# MagicWandFinal.net
KiCad netlist of a schematic drawn in Altium Designer
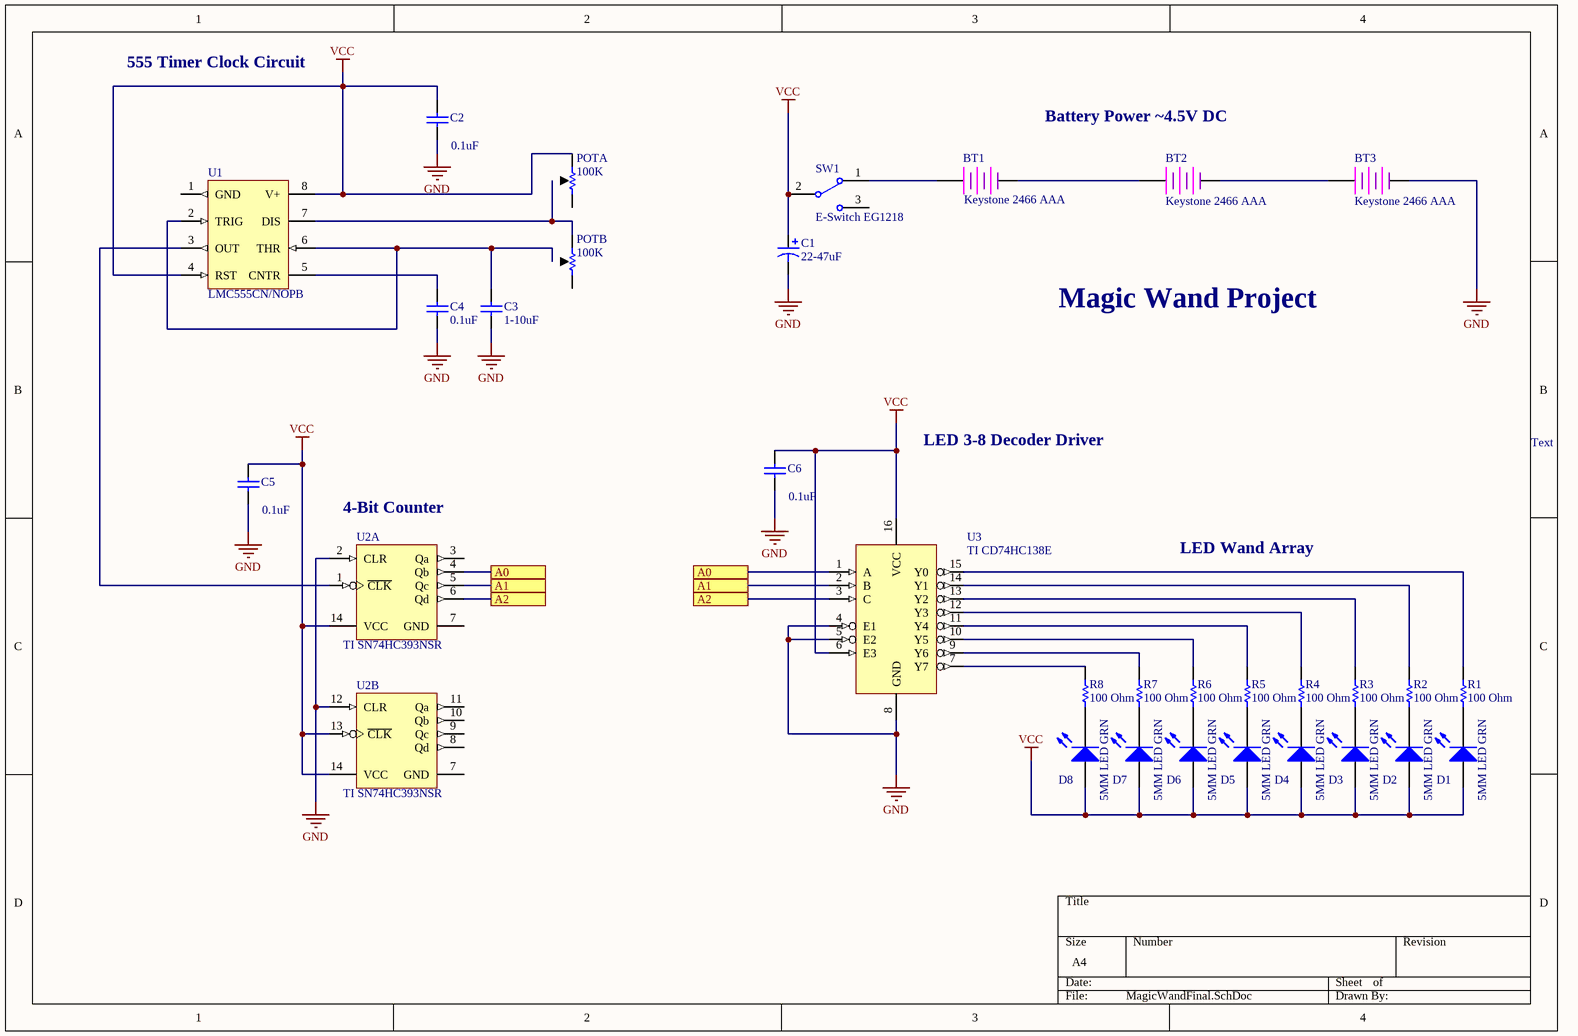
[diagram p0: MagicWandFinal.SchDoc]

(export (version "E")
  (design (tool "Eeschema 10.0.6"))
  (components
    (comp (ref "BT1")
      (value "Keystone 2466 AAA")
      (footprint "PCB-2466")
      (description "Battery holder, AAA, 1 cell, PC mount")
      (libsource (lib "My Personal Space") (part "SYM-2466"))
    )
    (comp (ref "BT2")
      (value "Keystone 2466 AAA")
      (footprint "PCB-2466")
      (description "Battery holder, AAA, 1 cell, PC mount")
      (libsource (lib "My Personal Space") (part "SYM-2466"))
    )
    (comp (ref "BT3")
      (value "Keystone 2466 AAA")
      (footprint "PCB-2466")
      (description "Battery holder, AAA, 1 cell, PC mount")
      (libsource (lib "My Personal Space") (part "SYM-2466"))
    )
    (comp (ref "C1")
      (value "22-47uF")
      (footprint "PCB-nq6yd78wv7rl8ojp8omb-1")
      (description "Cap Aluminum 10uF 16V 20% (4 X 7mm) Cylindrical 18mA 7000 hr 105°C T/R")
      (fields (field (name "MANUFACTURER PART NUMBER") "UCB1C100MCL1GS"))
      (libsource (lib "My Personal Space") (part "SYM-119dd9bbe86bce5a-1"))
    )
    (comp (ref "C2")
      (value "0.1uF")
      (footprint "PCB-ql28fbuo3tond8refhb5-1")
      (description "K 100nF Ceramic Multilayer Capacitor, 50 V dc, +125degC, X7R Dielectric, +/-10%")
      (libsource (lib "My Personal Space") (part "SYM-1272d9258f2acdb5-2"))
    )
    (comp (ref "C3")
      (value "1-10uF")
      (footprint "PCB-ql28fbuo3tond8refhb5-1")
      (description "K 100nF Ceramic Multilayer Capacitor, 50 V dc, +125degC, X7R Dielectric, +/-10%")
      (libsource (lib "My Personal Space") (part "SYM-1272d9258f2acdb5-2"))
    )
    (comp (ref "C4")
      (value "0.1uF")
      (footprint "PCB-ql28fbuo3tond8refhb5-1")
      (description "K 100nF Ceramic Multilayer Capacitor, 50 V dc, +125degC, X7R Dielectric, +/-10%")
      (libsource (lib "My Personal Space") (part "SYM-1272d9258f2acdb5-2"))
    )
    (comp (ref "C5")
      (value "0.1uF")
      (footprint "PCB-ql28fbuo3tond8refhb5-1")
      (description "K 100nF Ceramic Multilayer Capacitor, 50 V dc, +125degC, X7R Dielectric, +/-10%")
      (libsource (lib "My Personal Space") (part "SYM-1272d9258f2acdb5-2"))
    )
    (comp (ref "C6")
      (value "0.1uF")
      (footprint "PCB-ql28fbuo3tond8refhb5-1")
      (description "K 100nF Ceramic Multilayer Capacitor, 50 V dc, +125degC, X7R Dielectric, +/-10%")
      (libsource (lib "My Personal Space") (part "SYM-1272d9258f2acdb5-2"))
    )
    (comp (ref "D1")
      (value "5MM LED GRN")
      (footprint "PCB-b5vk7vz0xhkw7l0fnova-1")
      (description "LED Uni-Color Green 2-Pin T-1 3/4 Bulk")
      (fields
        (field (name "MANUFACTURER PART NUMBER") "C503B-GCN-CY0C0791")
        (field (name "MANUFACTURER") "Cree")
      )
      (libsource (lib "My Personal Space") (part "SYM-92bb5b2eff764d7c-1"))
    )
    (comp (ref "D2")
      (value "5MM LED GRN")
      (footprint "PCB-b5vk7vz0xhkw7l0fnova-1")
      (description "LED Uni-Color Green 2-Pin T-1 3/4 Bulk")
      (fields
        (field (name "MANUFACTURER PART NUMBER") "C503B-GCN-CY0C0791")
        (field (name "MANUFACTURER") "Cree")
      )
      (libsource (lib "My Personal Space") (part "SYM-92bb5b2eff764d7c-1"))
    )
    (comp (ref "D3")
      (value "5MM LED GRN")
      (footprint "PCB-b5vk7vz0xhkw7l0fnova-1")
      (description "LED Uni-Color Green 2-Pin T-1 3/4 Bulk")
      (fields
        (field (name "MANUFACTURER PART NUMBER") "C503B-GCN-CY0C0791")
        (field (name "MANUFACTURER") "Cree")
      )
      (libsource (lib "My Personal Space") (part "SYM-92bb5b2eff764d7c-1"))
    )
    (comp (ref "D4")
      (value "5MM LED GRN")
      (footprint "PCB-b5vk7vz0xhkw7l0fnova-1")
      (description "LED Uni-Color Green 2-Pin T-1 3/4 Bulk")
      (fields
        (field (name "MANUFACTURER PART NUMBER") "C503B-GCN-CY0C0791")
        (field (name "MANUFACTURER") "Cree")
      )
      (libsource (lib "My Personal Space") (part "SYM-92bb5b2eff764d7c-1"))
    )
    (comp (ref "D5")
      (value "5MM LED GRN")
      (footprint "PCB-b5vk7vz0xhkw7l0fnova-1")
      (description "LED Uni-Color Green 2-Pin T-1 3/4 Bulk")
      (fields
        (field (name "MANUFACTURER PART NUMBER") "C503B-GCN-CY0C0791")
        (field (name "MANUFACTURER") "Cree")
      )
      (libsource (lib "My Personal Space") (part "SYM-92bb5b2eff764d7c-1"))
    )
    (comp (ref "D6")
      (value "5MM LED GRN")
      (footprint "PCB-b5vk7vz0xhkw7l0fnova-1")
      (description "LED Uni-Color Green 2-Pin T-1 3/4 Bulk")
      (fields
        (field (name "MANUFACTURER PART NUMBER") "C503B-GCN-CY0C0791")
        (field (name "MANUFACTURER") "Cree")
      )
      (libsource (lib "My Personal Space") (part "SYM-92bb5b2eff764d7c-1"))
    )
    (comp (ref "D7")
      (value "5MM LED GRN")
      (footprint "PCB-b5vk7vz0xhkw7l0fnova-1")
      (description "LED Uni-Color Green 2-Pin T-1 3/4 Bulk")
      (fields
        (field (name "MANUFACTURER PART NUMBER") "C503B-GCN-CY0C0791")
        (field (name "MANUFACTURER") "Cree")
      )
      (libsource (lib "My Personal Space") (part "SYM-92bb5b2eff764d7c-1"))
    )
    (comp (ref "D8")
      (value "5MM LED GRN")
      (footprint "PCB-b5vk7vz0xhkw7l0fnova-1")
      (description "LED Uni-Color Green 2-Pin T-1 3/4 Bulk")
      (fields
        (field (name "MANUFACTURER PART NUMBER") "C503B-GCN-CY0C0791")
        (field (name "MANUFACTURER") "Cree")
      )
      (libsource (lib "My Personal Space") (part "SYM-92bb5b2eff764d7c-1"))
    )
    (comp (ref "POTA")
      (value "100K")
      (footprint "PCB-yu8b13vw5bhotm5v9joo-1")
      (description "Res Cermet Trimmer 200K Ohm 10% 1/2W 1(Elec)/1(Mech)Turn 2.6mm (7 X 7 X 5.8mm) Pin Thru-Hole Bulk")
      (fields (field (name "MANUFACTURER PART NUMBER") "CT-6EP204"))
      (libsource (lib "My Personal Space") (part "SYM-1c6ed013efbec3a9-1"))
    )
    (comp (ref "POTB")
      (value "100K")
      (footprint "PCB-yu8b13vw5bhotm5v9joo-1")
      (description "Res Cermet Trimmer 200K Ohm 10% 1/2W 1(Elec)/1(Mech)Turn 2.6mm (7 X 7 X 5.8mm) Pin Thru-Hole Bulk")
      (fields (field (name "MANUFACTURER PART NUMBER") "CT-6EP204"))
      (libsource (lib "My Personal Space") (part "SYM-1c6ed013efbec3a9-1"))
    )
    (comp (ref "R1")
      (value "100 Ohm")
      (footprint "PCB-0jk5y5qyb1smy9vf6b7t-1")
      (description "Res, 1K, 250mW, 5%, Axial")
      (libsource (lib "My Personal Space") (part "SYM-db3e1311f37e04f9-4"))
    )
    (comp (ref "R2")
      (value "100 Ohm")
      (footprint "PCB-0jk5y5qyb1smy9vf6b7t-1")
      (description "Res, 1K, 250mW, 5%, Axial")
      (libsource (lib "My Personal Space") (part "SYM-db3e1311f37e04f9-4"))
    )
    (comp (ref "R3")
      (value "100 Ohm")
      (footprint "PCB-0jk5y5qyb1smy9vf6b7t-1")
      (description "Res, 1K, 250mW, 5%, Axial")
      (libsource (lib "My Personal Space") (part "SYM-db3e1311f37e04f9-4"))
    )
    (comp (ref "R4")
      (value "100 Ohm")
      (footprint "PCB-0jk5y5qyb1smy9vf6b7t-1")
      (description "Res, 1K, 250mW, 5%, Axial")
      (libsource (lib "My Personal Space") (part "SYM-db3e1311f37e04f9-4"))
    )
    (comp (ref "R5")
      (value "100 Ohm")
      (footprint "PCB-0jk5y5qyb1smy9vf6b7t-1")
      (description "Res, 1K, 250mW, 5%, Axial")
      (libsource (lib "My Personal Space") (part "SYM-db3e1311f37e04f9-4"))
    )
    (comp (ref "R6")
      (value "100 Ohm")
      (footprint "PCB-0jk5y5qyb1smy9vf6b7t-1")
      (description "Res, 1K, 250mW, 5%, Axial")
      (libsource (lib "My Personal Space") (part "SYM-db3e1311f37e04f9-4"))
    )
    (comp (ref "R7")
      (value "100 Ohm")
      (footprint "PCB-0jk5y5qyb1smy9vf6b7t-1")
      (description "Res, 1K, 250mW, 5%, Axial")
      (libsource (lib "My Personal Space") (part "SYM-db3e1311f37e04f9-4"))
    )
    (comp (ref "R8")
      (value "100 Ohm")
      (footprint "PCB-0jk5y5qyb1smy9vf6b7t-1")
      (description "Res, 1K, 250mW, 5%, Axial")
      (libsource (lib "My Personal Space") (part "SYM-db3e1311f37e04f9-4"))
    )
    (comp (ref "SW1")
      (value "E-Switch EG1218")
      (footprint "ESWI-EG1218_V")
      (description "Slide Switch, 500 V, -20 to 70 degC, 3-Pin THD, RoHS")
      (fields (field (name "MANUFACTURER PART NUMBER") "EG1218"))
      (libsource (lib "My Personal Space") (part "SW-SPDT-3_B"))
    )
    (comp (ref "U1")
      (value "LMC555CN/NOPB")
      (footprint "TI-D8_L")
      (description "World’s smallest 555 timer with low power, high accuracy and a Fmax of 3MHz 8-SOIC -40 to 85")
      (fields (field (name "MANUFACTURER PART NUMBER") "LMC555CMX/NOPB"))
      (libsource (lib "My Personal Space") (part "INF-TLE5012BE5000-PG-DSO-8-16-8"))
    )
    (comp (ref "U2")
      (value "TI SN74HC393NSR")
      (footprint "SOIC-SL14_N")
      (description "Counter/Divider Dual 4-Bit Binary UP 14-Pin SOP T/R   SMD")
      (fields (field (name "MANUFACTURER PART NUMBER") "SN74HC393NSR"))
      (libsource (lib "My Personal Space") (part "SYM-3c53f5596157e394-1"))
    )
    (comp (ref "U3")
      (value "TI CD74HC138E")
      (footprint "PCB-iqyivjlmuk83cucpld0n-1")
      (description "TEXAS INSTRUMENTS   CD74HC138E   Logic Type:Decoder / Demultiplexer")
      (fields
        (field (name "MANUFACTURER") "Texas Instruments")
        (field (name "MANUFACTURER PART NUMBER") "CD74HC138E")
      )
      (libsource (lib "My Personal Space") (part "SYM-1166716-1"))
    )
  )
  (nets
    (net (code "1") (name "/A0") (class "Default")
      (node (ref "U2") (pin "4") (pinfunction "Qb_4") (pintype "output"))
      (node (ref "U3") (pin "1") (pinfunction "A_1") (pintype "input"))
    )
    (net (code "2") (name "/A1") (class "Default")
      (node (ref "U2") (pin "5") (pinfunction "Qc_5") (pintype "output"))
      (node (ref "U3") (pin "2") (pinfunction "B_2") (pintype "input"))
    )
    (net (code "3") (name "/A2") (class "Default")
      (node (ref "U2") (pin "6") (pinfunction "Qd_6") (pintype "output"))
      (node (ref "U3") (pin "3") (pinfunction "C_3") (pintype "input"))
    )
    (net (code "4") (name "GND") (class "Default")
      (node (ref "BT3") (pin "2") (pinfunction "-_2") (pintype "passive"))
      (node (ref "C1") (pin "2") (pinfunction "2_2") (pintype "passive"))
      (node (ref "C2") (pin "1") (pinfunction "1_1") (pintype "passive"))
      (node (ref "C3") (pin "1") (pinfunction "1_1") (pintype "passive"))
      (node (ref "C4") (pin "1") (pinfunction "1_1") (pintype "passive"))
      (node (ref "C5") (pin "1") (pinfunction "1_1") (pintype "passive"))
      (node (ref "C6") (pin "1") (pinfunction "1_1") (pintype "passive"))
      (node (ref "U2") (pin "12") (pinfunction "CLR_12") (pintype "input"))
      (node (ref "U2") (pin "2") (pinfunction "CLR_2") (pintype "input"))
      (node (ref "U3") (pin "4") (pinfunction "E1_4") (pintype "input"))
      (node (ref "U3") (pin "5") (pinfunction "E2_5") (pintype "input"))
      (node (ref "U3") (pin "8") (pinfunction "GND_8") (pintype "power_in"))
    )
    (net (code "5") (name "Net-(BT1-+)") (class "Default")
      (node (ref "BT1") (pin "1") (pinfunction "+_1") (pintype "passive"))
      (node (ref "SW1") (pin "1") (pinfunction "1_1") (pintype "passive"))
    )
    (net (code "6") (name "Net-(BT1--)") (class "Default")
      (node (ref "BT1") (pin "2") (pinfunction "-_2") (pintype "passive"))
      (node (ref "BT2") (pin "1") (pinfunction "+_1") (pintype "passive"))
    )
    (net (code "7") (name "Net-(BT2--)") (class "Default")
      (node (ref "BT2") (pin "2") (pinfunction "-_2") (pintype "passive"))
      (node (ref "BT3") (pin "1") (pinfunction "+_1") (pintype "passive"))
    )
    (net (code "8") (name "Net-(D1-K)") (class "Default")
      (node (ref "D1") (pin "1") (pinfunction "K_1") (pintype "passive"))
      (node (ref "R1") (pin "1") (pinfunction "1_1") (pintype "passive"))
    )
    (net (code "9") (name "Net-(D2-K)") (class "Default")
      (node (ref "D2") (pin "1") (pinfunction "K_1") (pintype "passive"))
      (node (ref "R2") (pin "1") (pinfunction "1_1") (pintype "passive"))
    )
    (net (code "10") (name "Net-(D3-K)") (class "Default")
      (node (ref "D3") (pin "1") (pinfunction "K_1") (pintype "passive"))
      (node (ref "R3") (pin "1") (pinfunction "1_1") (pintype "passive"))
    )
    (net (code "11") (name "Net-(D4-K)") (class "Default")
      (node (ref "D4") (pin "1") (pinfunction "K_1") (pintype "passive"))
      (node (ref "R4") (pin "1") (pinfunction "1_1") (pintype "passive"))
    )
    (net (code "12") (name "Net-(D5-K)") (class "Default")
      (node (ref "D5") (pin "1") (pinfunction "K_1") (pintype "passive"))
      (node (ref "R5") (pin "1") (pinfunction "1_1") (pintype "passive"))
    )
    (net (code "13") (name "Net-(D6-K)") (class "Default")
      (node (ref "D6") (pin "1") (pinfunction "K_1") (pintype "passive"))
      (node (ref "R6") (pin "1") (pinfunction "1_1") (pintype "passive"))
    )
    (net (code "14") (name "Net-(D7-K)") (class "Default")
      (node (ref "D7") (pin "1") (pinfunction "K_1") (pintype "passive"))
      (node (ref "R7") (pin "1") (pinfunction "1_1") (pintype "passive"))
    )
    (net (code "15") (name "Net-(D8-K)") (class "Default")
      (node (ref "D8") (pin "1") (pinfunction "K_1") (pintype "passive"))
      (node (ref "R8") (pin "1") (pinfunction "1_1") (pintype "passive"))
    )
    (net (code "16") (name "Net-(U1-CNTR)") (class "Default")
      (node (ref "C4") (pin "2") (pinfunction "2_2") (pintype "passive"))
      (node (ref "U1") (pin "5") (pinfunction "CNTR_5") (pintype "passive"))
    )
    (net (code "17") (name "Net-(U1-DIS)") (class "Default")
      (node (ref "POTA") (pin "2") (pinfunction "2_2") (pintype "passive"))
      (node (ref "POTB") (pin "1") (pinfunction "1_1") (pintype "passive"))
      (node (ref "U1") (pin "7") (pinfunction "DIS_7") (pintype "passive"))
    )
    (net (code "18") (name "Net-(U1-OUT)") (class "Default")
      (node (ref "U1") (pin "3") (pinfunction "OUT_3") (pintype "output"))
      (node (ref "U2") (pin "1") (pinfunction "~{CLK}_1") (pintype "input"))
    )
    (net (code "19") (name "Net-(U1-THR)") (class "Default")
      (node (ref "C3") (pin "2") (pinfunction "2_2") (pintype "passive"))
      (node (ref "POTB") (pin "2") (pinfunction "2_2") (pintype "passive"))
      (node (ref "U1") (pin "2") (pinfunction "TRIG_2") (pintype "input"))
      (node (ref "U1") (pin "6") (pinfunction "THR_6") (pintype "input"))
    )
    (net (code "20") (name "Net-(U3-Y0)") (class "Default")
      (node (ref "R1") (pin "2") (pinfunction "2_2") (pintype "passive"))
      (node (ref "U3") (pin "15") (pinfunction "Y0_15") (pintype "output"))
    )
    (net (code "21") (name "Net-(U3-Y1)") (class "Default")
      (node (ref "R2") (pin "2") (pinfunction "2_2") (pintype "passive"))
      (node (ref "U3") (pin "14") (pinfunction "Y1_14") (pintype "output"))
    )
    (net (code "22") (name "Net-(U3-Y2)") (class "Default")
      (node (ref "R3") (pin "2") (pinfunction "2_2") (pintype "passive"))
      (node (ref "U3") (pin "13") (pinfunction "Y2_13") (pintype "output"))
    )
    (net (code "23") (name "Net-(U3-Y3)") (class "Default")
      (node (ref "R4") (pin "2") (pinfunction "2_2") (pintype "passive"))
      (node (ref "U3") (pin "12") (pinfunction "Y3_12") (pintype "output"))
    )
    (net (code "24") (name "Net-(U3-Y4)") (class "Default")
      (node (ref "R5") (pin "2") (pinfunction "2_2") (pintype "passive"))
      (node (ref "U3") (pin "11") (pinfunction "Y4_11") (pintype "output"))
    )
    (net (code "25") (name "Net-(U3-Y5)") (class "Default")
      (node (ref "R6") (pin "2") (pinfunction "2_2") (pintype "passive"))
      (node (ref "U3") (pin "10") (pinfunction "Y5_10") (pintype "output"))
    )
    (net (code "26") (name "Net-(U3-Y6)") (class "Default")
      (node (ref "R7") (pin "2") (pinfunction "2_2") (pintype "passive"))
      (node (ref "U3") (pin "9") (pinfunction "Y6_9") (pintype "output"))
    )
    (net (code "27") (name "Net-(U3-Y7)") (class "Default")
      (node (ref "R8") (pin "2") (pinfunction "2_2") (pintype "passive"))
      (node (ref "U3") (pin "7") (pinfunction "Y7_7") (pintype "output"))
    )
    (net (code "28") (name "VCC") (class "Default")
      (node (ref "C1") (pin "1") (pinfunction "1_1") (pintype "passive"))
      (node (ref "C2") (pin "2") (pinfunction "2_2") (pintype "passive"))
      (node (ref "C5") (pin "2") (pinfunction "2_2") (pintype "passive"))
      (node (ref "C6") (pin "2") (pinfunction "2_2") (pintype "passive"))
      (node (ref "D1") (pin "2") (pinfunction "A_2") (pintype "passive"))
      (node (ref "D2") (pin "2") (pinfunction "A_2") (pintype "passive"))
      (node (ref "D3") (pin "2") (pinfunction "A_2") (pintype "passive"))
      (node (ref "D4") (pin "2") (pinfunction "A_2") (pintype "passive"))
      (node (ref "D5") (pin "2") (pinfunction "A_2") (pintype "passive"))
      (node (ref "D6") (pin "2") (pinfunction "A_2") (pintype "passive"))
      (node (ref "D7") (pin "2") (pinfunction "A_2") (pintype "passive"))
      (node (ref "D8") (pin "2") (pinfunction "A_2") (pintype "passive"))
      (node (ref "POTA") (pin "1") (pinfunction "1_1") (pintype "passive"))
      (node (ref "SW1") (pin "2") (pinfunction "COM_2") (pintype "passive"))
      (node (ref "U1") (pin "4") (pinfunction "RST_4") (pintype "input"))
      (node (ref "U1") (pin "8") (pinfunction "V+_8") (pintype "power_in"))
      (node (ref "U2") (pin "13") (pinfunction "~{CLK}_13") (pintype "input"))
      (node (ref "U2") (pin "14") (pinfunction "VCC_14") (pintype "power_in"))
      (node (ref "U3") (pin "16") (pinfunction "VCC_16") (pintype "power_in"))
      (node (ref "U3") (pin "6") (pinfunction "E3_6") (pintype "input"))
    )
    (net (code "29") (name "unconnected-(POTA-Pad3)") (class "Default")
      (node (ref "POTA") (pin "3") (pinfunction "3_3") (pintype "passive"))
    )
    (net (code "30") (name "unconnected-(POTB-Pad3)") (class "Default")
      (node (ref "POTB") (pin "3") (pinfunction "3_3") (pintype "passive"))
    )
    (net (code "31") (name "unconnected-(SW1-Pad3)") (class "Default")
      (node (ref "SW1") (pin "3") (pinfunction "3_3") (pintype "passive"))
    )
    (net (code "32") (name "unconnected-(U1-GND-Pad1)") (class "Default")
      (node (ref "U1") (pin "1") (pinfunction "GND_1") (pintype "output"))
    )
    (net (code "33") (name "unconnected-(U2A-GND-Pad7)") (class "Default")
      (node (ref "U2") (pin "7") (pinfunction "GND_7") (pintype "power_in"))
    )
    (net (code "34") (name "unconnected-(U2A-Qa-Pad3)") (class "Default")
      (node (ref "U2") (pin "3") (pinfunction "Qa_3") (pintype "output"))
    )
    (net (code "35") (name "unconnected-(U2B-GND-Pad7)") (class "Default")
      (node (ref "U2") (pin "7") (pinfunction "GND_7") (pintype "power_in"))
    )
    (net (code "36") (name "unconnected-(U2B-Qa-Pad11)") (class "Default")
      (node (ref "U2") (pin "11") (pinfunction "Qa_11") (pintype "output"))
    )
    (net (code "37") (name "unconnected-(U2B-Qb-Pad10)") (class "Default")
      (node (ref "U2") (pin "10") (pinfunction "Qb_10") (pintype "output"))
    )
    (net (code "38") (name "unconnected-(U2B-Qc-Pad9)") (class "Default")
      (node (ref "U2") (pin "9") (pinfunction "Qc_9") (pintype "output"))
    )
    (net (code "39") (name "unconnected-(U2B-Qd-Pad8)") (class "Default")
      (node (ref "U2") (pin "8") (pinfunction "Qd_8") (pintype "output"))
    )
  )
)
